# c100_rev_c.net
KiCad netlist of a schematic drawn in EAGLE
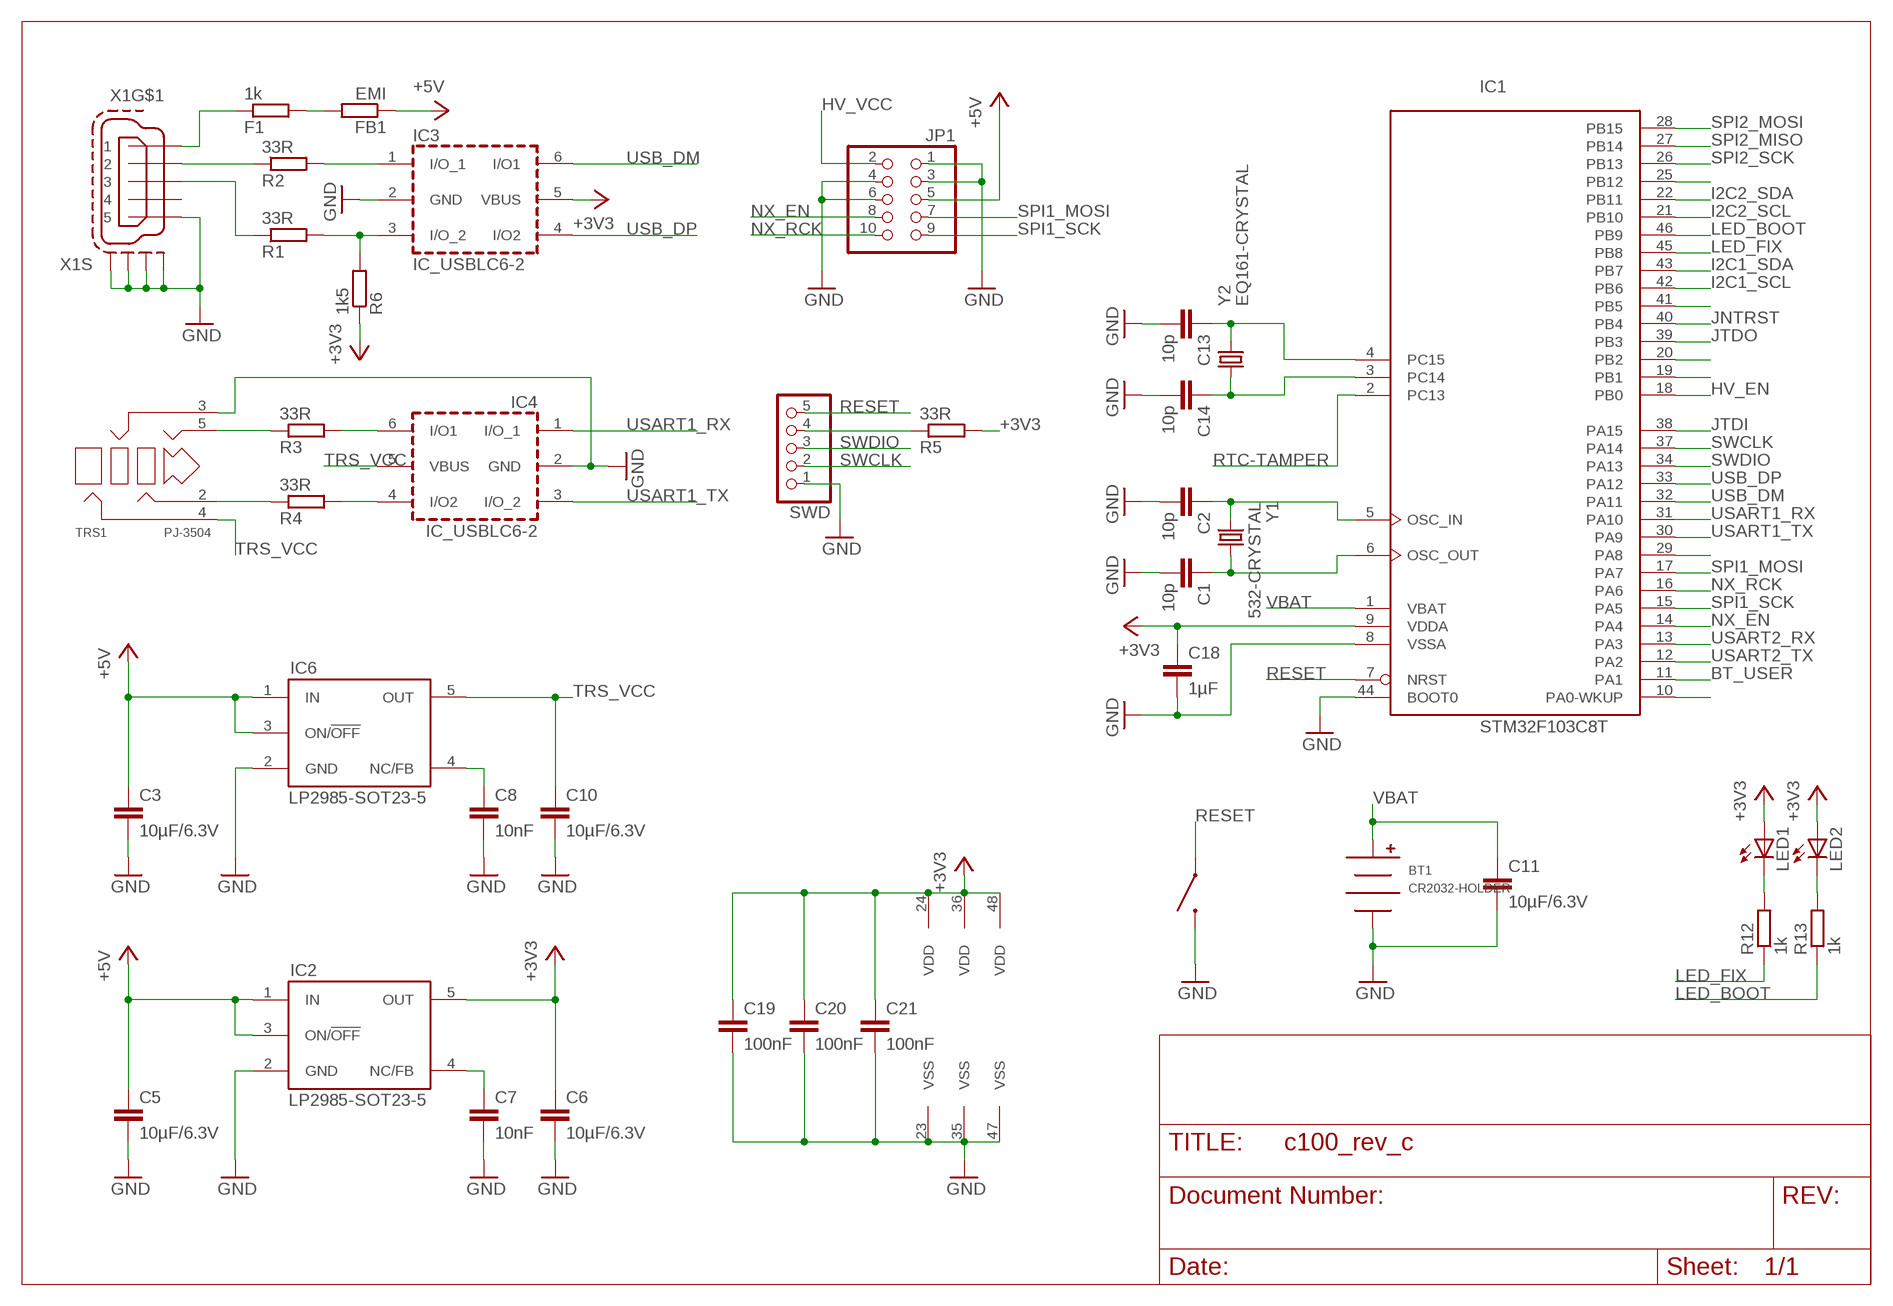
[diagram p0: schematic, sheet 1, part 1 of 2]
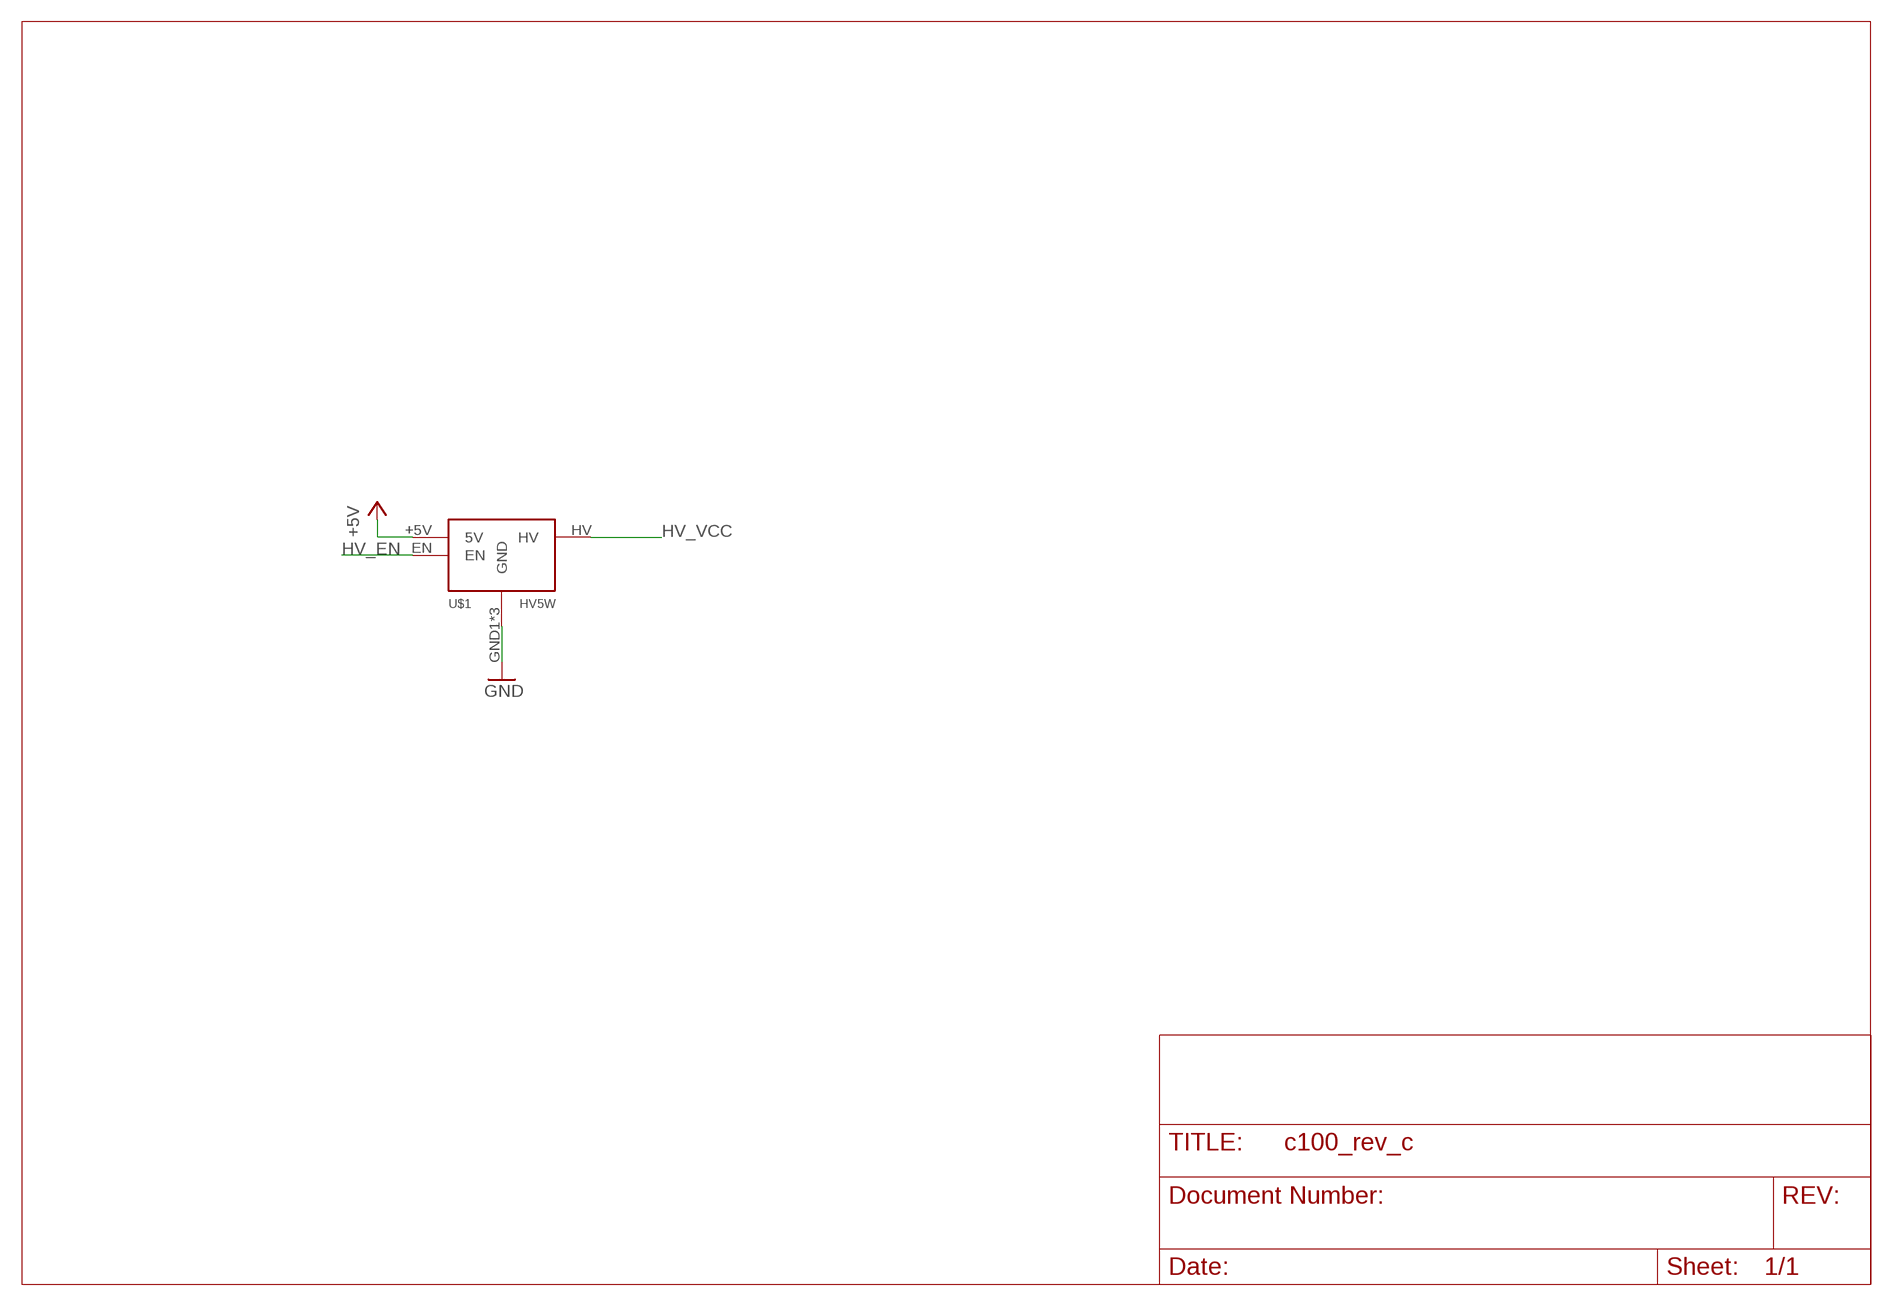
[diagram p1: schematic, sheet 1, part 2 of 2]

(export (version "E")
  (design (tool "Eeschema 10.0.6"))
  (components
    (comp (ref "BT1")
      (value "CR2032-HOLDER")
      (footprint "eagle-import:CH28-2032LF")
      (libsource (lib "eagle-import") (part "CR2032-HOLDER"))
    )
    (comp (ref "C1")
      (value "10p")
      (footprint "eagle-import:C0603")
      (libsource (lib "eagle-import") (part "C-EUC0603"))
    )
    (comp (ref "C2")
      (value "10p")
      (footprint "eagle-import:C0603")
      (libsource (lib "eagle-import") (part "C-EUC0603"))
    )
    (comp (ref "C3")
      (value "10µF/6.3V")
      (footprint "eagle-import:C0603")
      (libsource (lib "eagle-import") (part "C-EUC0603"))
    )
    (comp (ref "C5")
      (value "10µF/6.3V")
      (footprint "eagle-import:C0603")
      (libsource (lib "eagle-import") (part "C-EUC0603"))
    )
    (comp (ref "C6")
      (value "10µF/6.3V")
      (footprint "eagle-import:C0603")
      (libsource (lib "eagle-import") (part "C-EUC0603"))
    )
    (comp (ref "C7")
      (value "10nF")
      (footprint "eagle-import:C0603")
      (libsource (lib "eagle-import") (part "C-EUC0603"))
    )
    (comp (ref "C8")
      (value "10nF")
      (footprint "eagle-import:C0603")
      (libsource (lib "eagle-import") (part "C-EUC0603"))
    )
    (comp (ref "C10")
      (value "10µF/6.3V")
      (footprint "eagle-import:C0603")
      (libsource (lib "eagle-import") (part "C-EUC0603"))
    )
    (comp (ref "C11")
      (value "10µF/6.3V")
      (footprint "eagle-import:C0603")
      (libsource (lib "eagle-import") (part "C-EUC0603"))
    )
    (comp (ref "C13")
      (value "10p")
      (footprint "eagle-import:C0603")
      (libsource (lib "eagle-import") (part "C-EUC0603"))
    )
    (comp (ref "C14")
      (value "10p")
      (footprint "eagle-import:C0603")
      (libsource (lib "eagle-import") (part "C-EUC0603"))
    )
    (comp (ref "C18")
      (value "1µF")
      (footprint "eagle-import:C0603")
      (libsource (lib "eagle-import") (part "C-EUC0603"))
    )
    (comp (ref "C19")
      (value "100nF")
      (footprint "eagle-import:C0603")
      (libsource (lib "eagle-import") (part "C-EUC0603"))
    )
    (comp (ref "C20")
      (value "100nF")
      (footprint "eagle-import:C0603")
      (libsource (lib "eagle-import") (part "C-EUC0603"))
    )
    (comp (ref "C21")
      (value "100nF")
      (footprint "eagle-import:C0603")
      (libsource (lib "eagle-import") (part "C-EUC0603"))
    )
    (comp (ref "F1")
      (value "1k")
      (footprint "eagle-import:R0603")
      (libsource (lib "eagle-import") (part "R-EU_R0603"))
    )
    (comp (ref "FB1")
      (value "EMI")
      (footprint "eagle-import:R0603")
      (libsource (lib "eagle-import") (part "R-EU_R0603"))
    )
    (comp (ref "IC1")
      (value "STM32F103C8T")
      (footprint "eagle-import:LQFP48")
      (libsource (lib "eagle-import") (part "STM32F103CT8"))
    )
    (comp (ref "IC2")
      (value "LP2985-SOT23-5")
      (footprint "eagle-import:SOT23-5")
      (libsource (lib "eagle-import") (part "LP2985-SOT23-5"))
    )
    (comp (ref "IC3")
      (value "IC_USBLC6-2")
      (footprint "eagle-import:SOT-23-6L")
      (libsource (lib "eagle-import") (part "IC_USBLC6-2"))
    )
    (comp (ref "IC4")
      (value "IC_USBLC6-2")
      (footprint "eagle-import:SOT-23-6L")
      (libsource (lib "eagle-import") (part "IC_USBLC6-2"))
    )
    (comp (ref "IC6")
      (value "LP2985-SOT23-5")
      (footprint "eagle-import:SOT23-5")
      (libsource (lib "eagle-import") (part "LP2985-SOT23-5"))
    )
    (comp (ref "ISP")
      (value "TACT-SWITCH-40-40")
      (footprint "eagle-import:40-40")
      (libsource (lib "eagle-import") (part "TACT-SWITCH-40-40"))
    )
    (comp (ref "JP1")
      (value "PINHD-2X5_2.54-SMD")
      (footprint "eagle-import:2X05SMD")
      (libsource (lib "eagle-import") (part "PINHD-2X5_2.54-SMD"))
    )
    (comp (ref "LED1")
      (value "LEDCHIP-LED0603")
      (footprint "eagle-import:CHIP-LED0603")
      (libsource (lib "eagle-import") (part "LEDCHIP-LED0603"))
    )
    (comp (ref "LED2")
      (value "LEDCHIP-LED0603")
      (footprint "eagle-import:CHIP-LED0603")
      (libsource (lib "eagle-import") (part "LEDCHIP-LED0603"))
    )
    (comp (ref "R1")
      (value "33R")
      (footprint "eagle-import:R0603")
      (libsource (lib "eagle-import") (part "R-EU_R0603"))
    )
    (comp (ref "R2")
      (value "33R")
      (footprint "eagle-import:R0603")
      (libsource (lib "eagle-import") (part "R-EU_R0603"))
    )
    (comp (ref "R3")
      (value "33R")
      (footprint "eagle-import:R0603")
      (libsource (lib "eagle-import") (part "R-EU_R0603"))
    )
    (comp (ref "R4")
      (value "33R")
      (footprint "eagle-import:R0603")
      (libsource (lib "eagle-import") (part "R-EU_R0603"))
    )
    (comp (ref "R5")
      (value "33R")
      (footprint "eagle-import:R0603")
      (libsource (lib "eagle-import") (part "R-EU_R0603"))
    )
    (comp (ref "R6")
      (value "1k5")
      (footprint "eagle-import:R0603")
      (libsource (lib "eagle-import") (part "R-EU_R0603"))
    )
    (comp (ref "R12")
      (value "1k")
      (footprint "eagle-import:R0603")
      (libsource (lib "eagle-import") (part "R-EU_R0603"))
    )
    (comp (ref "R13")
      (value "1k")
      (footprint "eagle-import:R0603")
      (libsource (lib "eagle-import") (part "R-EU_R0603"))
    )
    (comp (ref "SWD")
      (value "HEADER-1X5ROUND")
      (footprint "eagle-import:1X05_ROUND")
      (libsource (lib "eagle-import") (part "HEADER-1X5ROUND"))
    )
    (comp (ref "TRS1")
      (value "PJ-3504")
      (footprint "eagle-import:YD-PJ-3504")
      (libsource (lib "eagle-import") (part "PJ-3504"))
    )
    (comp (ref "U$1")
      (value "HV5W")
      (footprint "eagle-import:HV5W-D")
      (libsource (lib "eagle-import") (part "HV5W"))
    )
    (comp (ref "X1")
      (value "MINI-USB-SCHIELD-32005-201")
      (footprint "eagle-import:32005-201")
      (libsource (lib "eagle-import") (part "MINI-USB-SCHIELD-32005-201"))
    )
    (comp (ref "Y1")
      (value "532-CRYSTAL")
      (footprint "eagle-import:2PIN50X32")
      (libsource (lib "eagle-import") (part "532-CRYSTAL"))
    )
    (comp (ref "Y2")
      (value "EQ161-CRYSTAL")
      (footprint "eagle-import:EQ161")
      (libsource (lib "eagle-import") (part "EQ161-CRYSTAL"))
    )
  )
  (nets
    (net (code "1") (name "+3V3") (class "Default")
      (node (ref "C18") (pin "1") (pinfunction "1_1") (pintype "passive"))
      (node (ref "C19") (pin "1") (pinfunction "1_1") (pintype "passive"))
      (node (ref "C20") (pin "1") (pinfunction "1_1") (pintype "passive"))
      (node (ref "C21") (pin "1") (pinfunction "1_1") (pintype "passive"))
      (node (ref "C6") (pin "1") (pinfunction "1_1") (pintype "passive"))
      (node (ref "IC1") (pin "24") (pinfunction "VDD_24") (pintype "power_in"))
      (node (ref "IC1") (pin "36") (pinfunction "VDD_36") (pintype "power_in"))
      (node (ref "IC1") (pin "48") (pinfunction "VDD_48") (pintype "power_in"))
      (node (ref "IC1") (pin "9") (pinfunction "VDDA_9") (pintype "power_in"))
      (node (ref "IC2") (pin "5") (pinfunction "OUT_5") (pintype "bidirectional"))
      (node (ref "IC3") (pin "5") (pinfunction "VBUS_5") (pintype "bidirectional"))
      (node (ref "LED1") (pin "A") (pinfunction "A_A") (pintype "passive"))
      (node (ref "LED2") (pin "A") (pinfunction "A_A") (pintype "passive"))
      (node (ref "R5") (pin "2") (pinfunction "2_2") (pintype "passive"))
      (node (ref "R6") (pin "1") (pinfunction "1_1") (pintype "passive"))
    )
    (net (code "2") (name "+5V") (class "Default")
      (node (ref "C3") (pin "1") (pinfunction "1_1") (pintype "passive"))
      (node (ref "C5") (pin "1") (pinfunction "1_1") (pintype "passive"))
      (node (ref "FB1") (pin "1") (pinfunction "1_1") (pintype "passive"))
      (node (ref "IC2") (pin "1") (pinfunction "IN_1") (pintype "bidirectional"))
      (node (ref "IC2") (pin "3") (pinfunction "ON/~{OFF}_3") (pintype "bidirectional"))
      (node (ref "IC6") (pin "1") (pinfunction "IN_1") (pintype "bidirectional"))
      (node (ref "IC6") (pin "3") (pinfunction "ON/~{OFF}_3") (pintype "bidirectional"))
      (node (ref "JP1") (pin "5") (pinfunction "5_5") (pintype "passive"))
      (node (ref "U$1") (pin "+5V") (pinfunction "5V_+5V") (pintype "bidirectional"))
    )
    (net (code "3") (name "/BT_USER") (class "Default")
      (node (ref "IC1") (pin "11") (pinfunction "PA1_11") (pintype "bidirectional"))
    )
    (net (code "4") (name "/HV_EN") (class "Default")
      (node (ref "IC1") (pin "18") (pinfunction "PB0_18") (pintype "bidirectional"))
      (node (ref "U$1") (pin "EN") (pinfunction "EN_EN") (pintype "bidirectional"))
    )
    (net (code "5") (name "/HV_VCC") (class "Default")
      (node (ref "JP1") (pin "2") (pinfunction "2_2") (pintype "passive"))
      (node (ref "U$1") (pin "HV") (pinfunction "HV_HV") (pintype "bidirectional"))
    )
    (net (code "6") (name "/I2C1_SCL") (class "Default")
      (node (ref "IC1") (pin "42") (pinfunction "PB6_42") (pintype "bidirectional"))
    )
    (net (code "7") (name "/I2C1_SDA") (class "Default")
      (node (ref "IC1") (pin "43") (pinfunction "PB7_43") (pintype "bidirectional"))
    )
    (net (code "8") (name "/I2C2_SCL") (class "Default")
      (node (ref "IC1") (pin "21") (pinfunction "PB10_21") (pintype "bidirectional"))
    )
    (net (code "9") (name "/I2C2_SDA") (class "Default")
      (node (ref "IC1") (pin "22") (pinfunction "PB11_22") (pintype "bidirectional"))
    )
    (net (code "10") (name "/JNTRST") (class "Default")
      (node (ref "IC1") (pin "40") (pinfunction "PB4_40") (pintype "bidirectional"))
    )
    (net (code "11") (name "/JTDI") (class "Default")
      (node (ref "IC1") (pin "38") (pinfunction "PA15_38") (pintype "bidirectional"))
    )
    (net (code "12") (name "/JTDO") (class "Default")
      (node (ref "IC1") (pin "39") (pinfunction "PB3_39") (pintype "bidirectional"))
    )
    (net (code "13") (name "/LED_BOOT") (class "Default")
      (node (ref "IC1") (pin "46") (pinfunction "PB9_46") (pintype "bidirectional"))
      (node (ref "R13") (pin "1") (pinfunction "1_1") (pintype "passive"))
    )
    (net (code "14") (name "/LED_FIX") (class "Default")
      (node (ref "IC1") (pin "45") (pinfunction "PB8_45") (pintype "bidirectional"))
      (node (ref "R12") (pin "1") (pinfunction "1_1") (pintype "passive"))
    )
    (net (code "15") (name "/NX_EN") (class "Default")
      (node (ref "IC1") (pin "14") (pinfunction "PA4_14") (pintype "bidirectional"))
      (node (ref "JP1") (pin "8") (pinfunction "8_8") (pintype "passive"))
    )
    (net (code "16") (name "/NX_RCK") (class "Default")
      (node (ref "IC1") (pin "16") (pinfunction "PA6_16") (pintype "bidirectional"))
      (node (ref "JP1") (pin "10") (pinfunction "10_10") (pintype "passive"))
    )
    (net (code "17") (name "/RESET") (class "Default")
      (node (ref "IC1") (pin "7") (pinfunction "NRST_7") (pintype "bidirectional"))
      (node (ref "ISP") (pin "3") (pinfunction "P$2_3") (pintype "bidirectional"))
      (node (ref "ISP") (pin "4") (pinfunction "P$2_4") (pintype "bidirectional"))
      (node (ref "SWD") (pin "5") (pinfunction "5_5") (pintype "passive"))
    )
    (net (code "18") (name "/RTC-TAMPER") (class "Default")
      (node (ref "IC1") (pin "2") (pinfunction "PC13_2") (pintype "bidirectional"))
    )
    (net (code "19") (name "/SPI1_MOSI") (class "Default")
      (node (ref "IC1") (pin "17") (pinfunction "PA7_17") (pintype "bidirectional"))
      (node (ref "JP1") (pin "7") (pinfunction "7_7") (pintype "passive"))
    )
    (net (code "20") (name "/SPI1_SCK") (class "Default")
      (node (ref "IC1") (pin "15") (pinfunction "PA5_15") (pintype "bidirectional"))
      (node (ref "JP1") (pin "9") (pinfunction "9_9") (pintype "passive"))
    )
    (net (code "21") (name "/SPI2_MISO") (class "Default")
      (node (ref "IC1") (pin "27") (pinfunction "PB14_27") (pintype "bidirectional"))
    )
    (net (code "22") (name "/SPI2_MOSI") (class "Default")
      (node (ref "IC1") (pin "28") (pinfunction "PB15_28") (pintype "bidirectional"))
    )
    (net (code "23") (name "/SPI2_SCK") (class "Default")
      (node (ref "IC1") (pin "26") (pinfunction "PB13_26") (pintype "bidirectional"))
    )
    (net (code "24") (name "/SWCLK") (class "Default")
      (node (ref "IC1") (pin "37") (pinfunction "PA14_37") (pintype "bidirectional"))
      (node (ref "SWD") (pin "2") (pinfunction "2_2") (pintype "passive"))
    )
    (net (code "25") (name "/SWDIO") (class "Default")
      (node (ref "IC1") (pin "34") (pinfunction "PA13_34") (pintype "bidirectional"))
      (node (ref "SWD") (pin "3") (pinfunction "3_3") (pintype "passive"))
    )
    (net (code "26") (name "/TRS_VCC") (class "Default")
      (node (ref "C10") (pin "1") (pinfunction "1_1") (pintype "passive"))
      (node (ref "IC4") (pin "5") (pinfunction "VBUS_5") (pintype "bidirectional"))
      (node (ref "IC6") (pin "5") (pinfunction "OUT_5") (pintype "bidirectional"))
      (node (ref "TRS1") (pin "4") (pinfunction "4_4") (pintype "bidirectional"))
    )
    (net (code "27") (name "/USART1_RX") (class "Default")
      (node (ref "IC1") (pin "31") (pinfunction "PA10_31") (pintype "bidirectional"))
      (node (ref "IC4") (pin "1") (pinfunction "I/O_1_1") (pintype "bidirectional"))
    )
    (net (code "28") (name "/USART1_TX") (class "Default")
      (node (ref "IC1") (pin "30") (pinfunction "PA9_30") (pintype "bidirectional"))
      (node (ref "IC4") (pin "3") (pinfunction "I/O_2_3") (pintype "bidirectional"))
    )
    (net (code "29") (name "/USART2_RX") (class "Default")
      (node (ref "IC1") (pin "13") (pinfunction "PA3_13") (pintype "bidirectional"))
    )
    (net (code "30") (name "/USART2_TX") (class "Default")
      (node (ref "IC1") (pin "12") (pinfunction "PA2_12") (pintype "bidirectional"))
    )
    (net (code "31") (name "/USB_DM") (class "Default")
      (node (ref "IC1") (pin "32") (pinfunction "PA11_32") (pintype "bidirectional"))
      (node (ref "IC3") (pin "6") (pinfunction "I/O1_6") (pintype "bidirectional"))
    )
    (net (code "32") (name "/USB_DP") (class "Default")
      (node (ref "IC1") (pin "33") (pinfunction "PA12_33") (pintype "bidirectional"))
      (node (ref "IC3") (pin "4") (pinfunction "I/O2_4") (pintype "bidirectional"))
    )
    (net (code "33") (name "/VBAT") (class "Default")
      (node (ref "BT1") (pin "POS") (pinfunction "POS_POS") (pintype "bidirectional"))
      (node (ref "C11") (pin "1") (pinfunction "1_1") (pintype "passive"))
      (node (ref "IC1") (pin "1") (pinfunction "VBAT_1") (pintype "power_in"))
    )
    (net (code "34") (name "GND") (class "Default")
      (node (ref "BT1") (pin "NEG") (pinfunction "NEG_NEG") (pintype "bidirectional"))
      (node (ref "C1") (pin "2") (pinfunction "2_2") (pintype "passive"))
      (node (ref "C10") (pin "2") (pinfunction "2_2") (pintype "passive"))
      (node (ref "C11") (pin "2") (pinfunction "2_2") (pintype "passive"))
      (node (ref "C13") (pin "2") (pinfunction "2_2") (pintype "passive"))
      (node (ref "C14") (pin "2") (pinfunction "2_2") (pintype "passive"))
      (node (ref "C18") (pin "2") (pinfunction "2_2") (pintype "passive"))
      (node (ref "C19") (pin "2") (pinfunction "2_2") (pintype "passive"))
      (node (ref "C2") (pin "2") (pinfunction "2_2") (pintype "passive"))
      (node (ref "C20") (pin "2") (pinfunction "2_2") (pintype "passive"))
      (node (ref "C21") (pin "2") (pinfunction "2_2") (pintype "passive"))
      (node (ref "C3") (pin "2") (pinfunction "2_2") (pintype "passive"))
      (node (ref "C5") (pin "2") (pinfunction "2_2") (pintype "passive"))
      (node (ref "C6") (pin "2") (pinfunction "2_2") (pintype "passive"))
      (node (ref "C7") (pin "2") (pinfunction "2_2") (pintype "passive"))
      (node (ref "C8") (pin "2") (pinfunction "2_2") (pintype "passive"))
      (node (ref "IC1") (pin "23") (pinfunction "VSS_23") (pintype "power_in"))
      (node (ref "IC1") (pin "35") (pinfunction "VSS_35") (pintype "power_in"))
      (node (ref "IC1") (pin "44") (pinfunction "BOOT0_44") (pintype "input"))
      (node (ref "IC1") (pin "47") (pinfunction "VSS_47") (pintype "power_in"))
      (node (ref "IC1") (pin "8") (pinfunction "VSSA_8") (pintype "power_in"))
      (node (ref "IC2") (pin "2") (pinfunction "GND_2") (pintype "bidirectional"))
      (node (ref "IC3") (pin "2") (pinfunction "GND_2") (pintype "bidirectional"))
      (node (ref "IC4") (pin "2") (pinfunction "GND_2") (pintype "bidirectional"))
      (node (ref "IC6") (pin "2") (pinfunction "GND_2") (pintype "bidirectional"))
      (node (ref "ISP") (pin "1") (pinfunction "P$1_1") (pintype "bidirectional"))
      (node (ref "ISP") (pin "2") (pinfunction "P$1_2") (pintype "bidirectional"))
      (node (ref "JP1") (pin "1") (pinfunction "1_1") (pintype "passive"))
      (node (ref "JP1") (pin "3") (pinfunction "3_3") (pintype "passive"))
      (node (ref "JP1") (pin "4") (pinfunction "4_4") (pintype "passive"))
      (node (ref "JP1") (pin "6") (pinfunction "6_6") (pintype "passive"))
      (node (ref "SWD") (pin "1") (pinfunction "1_1") (pintype "passive"))
      (node (ref "TRS1") (pin "3") (pinfunction "3_3") (pintype "bidirectional"))
      (node (ref "U$1") (pin "GND1") (pinfunction "GND_GND1") (pintype "bidirectional"))
      (node (ref "U$1") (pin "GND2") (pinfunction "GND_GND2") (pintype "bidirectional"))
      (node (ref "U$1") (pin "GND3") (pinfunction "GND_GND3") (pintype "bidirectional"))
      (node (ref "X1") (pin "5") (pinfunction "5_5") (pintype "passive"))
      (node (ref "X1") (pin "M1") (pinfunction "S1_M1") (pintype "passive"))
      (node (ref "X1") (pin "M2") (pinfunction "S2_M2") (pintype "passive"))
      (node (ref "X1") (pin "M3") (pinfunction "S3_M3") (pintype "passive"))
      (node (ref "X1") (pin "M4") (pinfunction "S4_M4") (pintype "passive"))
    )
    (net (code "35") (name "Net-(F1-Pad1)") (class "Default")
      (node (ref "F1") (pin "1") (pinfunction "1_1") (pintype "passive"))
      (node (ref "X1") (pin "1") (pinfunction "1_1") (pintype "passive"))
    )
    (net (code "36") (name "Net-(F1-Pad2)") (class "Default")
      (node (ref "F1") (pin "2") (pinfunction "2_2") (pintype "passive"))
      (node (ref "FB1") (pin "2") (pinfunction "2_2") (pintype "passive"))
    )
    (net (code "37") (name "Net-(IC1A-OSC_IN)") (class "Default")
      (node (ref "C2") (pin "1") (pinfunction "1_1") (pintype "passive"))
      (node (ref "IC1") (pin "5") (pinfunction "OSC_IN_5") (pintype "bidirectional"))
      (node (ref "Y1") (pin "P$2") (pinfunction "2_P$2") (pintype "passive"))
    )
    (net (code "38") (name "Net-(IC1A-OSC_OUT)") (class "Default")
      (node (ref "C1") (pin "1") (pinfunction "1_1") (pintype "passive"))
      (node (ref "IC1") (pin "6") (pinfunction "OSC_OUT_6") (pintype "bidirectional"))
      (node (ref "Y1") (pin "P$1") (pinfunction "1_P$1") (pintype "passive"))
    )
    (net (code "39") (name "Net-(IC1A-PC14)") (class "Default")
      (node (ref "C14") (pin "1") (pinfunction "1_1") (pintype "passive"))
      (node (ref "IC1") (pin "3") (pinfunction "PC14_3") (pintype "bidirectional"))
      (node (ref "Y2") (pin "P$2") (pinfunction "2_P$2") (pintype "passive"))
    )
    (net (code "40") (name "Net-(IC1A-PC15)") (class "Default")
      (node (ref "C13") (pin "1") (pinfunction "1_1") (pintype "passive"))
      (node (ref "IC1") (pin "4") (pinfunction "PC15_4") (pintype "bidirectional"))
      (node (ref "Y2") (pin "P$1") (pinfunction "1_P$1") (pintype "passive"))
    )
    (net (code "41") (name "Net-(IC2-NC{slash}FB)") (class "Default")
      (node (ref "C7") (pin "1") (pinfunction "1_1") (pintype "passive"))
      (node (ref "IC2") (pin "4") (pinfunction "NC/FB_4") (pintype "bidirectional"))
    )
    (net (code "42") (name "Net-(IC3-I{slash}O_1)") (class "Default")
      (node (ref "IC3") (pin "1") (pinfunction "I/O_1_1") (pintype "bidirectional"))
      (node (ref "R2") (pin "2") (pinfunction "2_2") (pintype "passive"))
    )
    (net (code "43") (name "Net-(IC3-I{slash}O_2)") (class "Default")
      (node (ref "IC3") (pin "3") (pinfunction "I/O_2_3") (pintype "bidirectional"))
      (node (ref "R1") (pin "2") (pinfunction "2_2") (pintype "passive"))
      (node (ref "R6") (pin "2") (pinfunction "2_2") (pintype "passive"))
    )
    (net (code "44") (name "Net-(IC4-I{slash}O1)") (class "Default")
      (node (ref "IC4") (pin "6") (pinfunction "I/O1_6") (pintype "bidirectional"))
      (node (ref "R3") (pin "2") (pinfunction "2_2") (pintype "passive"))
    )
    (net (code "45") (name "Net-(IC4-I{slash}O2)") (class "Default")
      (node (ref "IC4") (pin "4") (pinfunction "I/O2_4") (pintype "bidirectional"))
      (node (ref "R4") (pin "2") (pinfunction "2_2") (pintype "passive"))
    )
    (net (code "46") (name "Net-(IC6-NC{slash}FB)") (class "Default")
      (node (ref "C8") (pin "1") (pinfunction "1_1") (pintype "passive"))
      (node (ref "IC6") (pin "4") (pinfunction "NC/FB_4") (pintype "bidirectional"))
    )
    (net (code "47") (name "Net-(LED1-PadC)") (class "Default")
      (node (ref "LED1") (pin "C") (pinfunction "C_C") (pintype "passive"))
      (node (ref "R12") (pin "2") (pinfunction "2_2") (pintype "passive"))
    )
    (net (code "48") (name "Net-(LED2-PadC)") (class "Default")
      (node (ref "LED2") (pin "C") (pinfunction "C_C") (pintype "passive"))
      (node (ref "R13") (pin "2") (pinfunction "2_2") (pintype "passive"))
    )
    (net (code "49") (name "Net-(R1-Pad1)") (class "Default")
      (node (ref "R1") (pin "1") (pinfunction "1_1") (pintype "passive"))
      (node (ref "X1") (pin "3") (pinfunction "3_3") (pintype "passive"))
    )
    (net (code "50") (name "Net-(R2-Pad1)") (class "Default")
      (node (ref "R2") (pin "1") (pinfunction "1_1") (pintype "passive"))
      (node (ref "X1") (pin "2") (pinfunction "2_2") (pintype "passive"))
    )
    (net (code "51") (name "Net-(R3-Pad1)") (class "Default")
      (node (ref "R3") (pin "1") (pinfunction "1_1") (pintype "passive"))
      (node (ref "TRS1") (pin "5") (pinfunction "5_5") (pintype "bidirectional"))
    )
    (net (code "52") (name "Net-(R4-Pad1)") (class "Default")
      (node (ref "R4") (pin "1") (pinfunction "1_1") (pintype "passive"))
      (node (ref "TRS1") (pin "2") (pinfunction "2_2") (pintype "bidirectional"))
    )
    (net (code "53") (name "Net-(R5-Pad1)") (class "Default")
      (node (ref "R5") (pin "1") (pinfunction "1_1") (pintype "passive"))
      (node (ref "SWD") (pin "4") (pinfunction "4_4") (pintype "passive"))
    )
    (net (code "54") (name "unconnected-(IC1A-PA0-WKUP-Pad10)") (class "Default")
      (node (ref "IC1") (pin "10") (pinfunction "PA0-WKUP_10") (pintype "bidirectional"))
    )
    (net (code "55") (name "unconnected-(IC1A-PA8-Pad29)") (class "Default")
      (node (ref "IC1") (pin "29") (pinfunction "PA8_29") (pintype "bidirectional"))
    )
    (net (code "56") (name "unconnected-(IC1A-PB1-Pad19)") (class "Default")
      (node (ref "IC1") (pin "19") (pinfunction "PB1_19") (pintype "bidirectional"))
    )
    (net (code "57") (name "unconnected-(IC1A-PB2-Pad20)") (class "Default")
      (node (ref "IC1") (pin "20") (pinfunction "PB2_20") (pintype "bidirectional"))
    )
    (net (code "58") (name "unconnected-(IC1A-PB5-Pad41)") (class "Default")
      (node (ref "IC1") (pin "41") (pinfunction "PB5_41") (pintype "bidirectional"))
    )
    (net (code "59") (name "unconnected-(IC1A-PB12-Pad25)") (class "Default")
      (node (ref "IC1") (pin "25") (pinfunction "PB12_25") (pintype "bidirectional"))
    )
    (net (code "60") (name "unconnected-(X1-Pad4)") (class "Default")
      (node (ref "X1") (pin "4") (pinfunction "4_4") (pintype "passive"))
    )
  )
)
